# Sheet1.net
KiCad netlist of a schematic drawn in Altium Designer
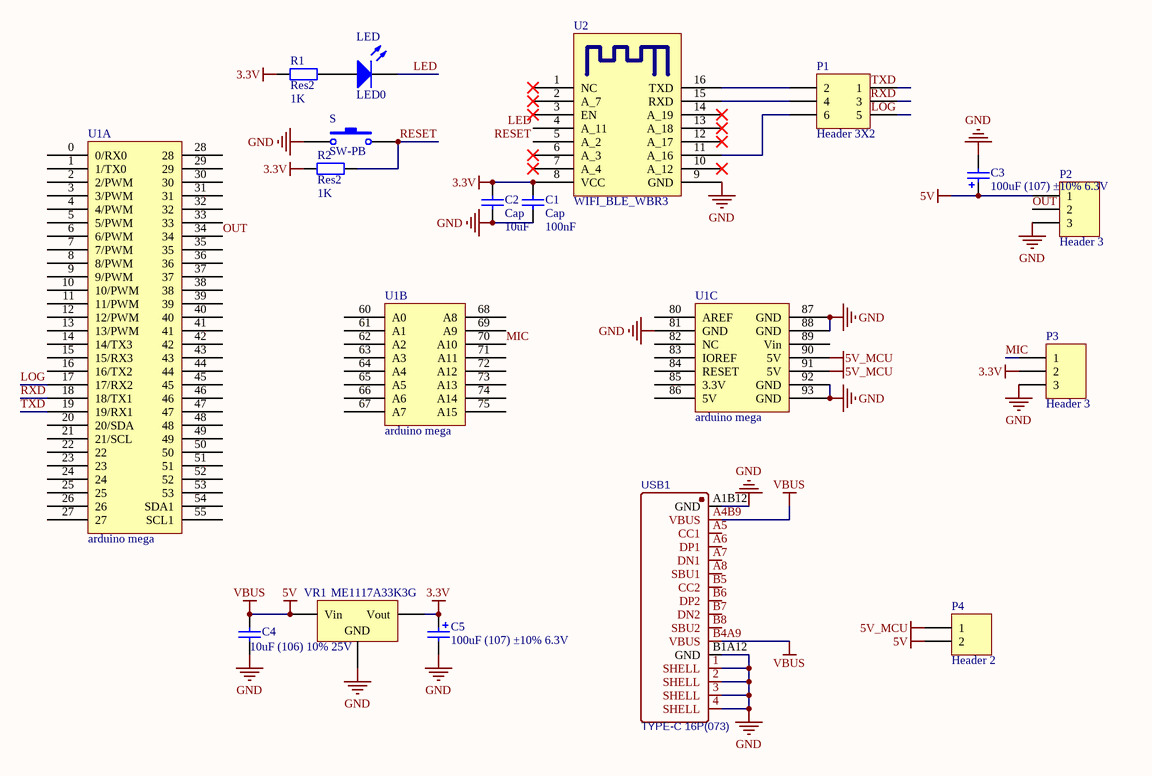
[diagram p0: Sheet1.SchDoc]

(export (version "E")
  (design (tool "Eeschema 10.0.6"))
  (components
    (comp (ref "C1")
      (value "Cap")
      (footprint "C 0603_L")
      (description "Capacitor")
      (fields (field (name "ALTIUM_VALUE") "100nF") (field (name "PUBLISHER") "Altium Limited"))
      (libsource (lib "Miscellaneous Devices") (part "Cap"))
    )
    (comp (ref "C2")
      (value "Cap")
      (footprint "C 0805_L")
      (description "Capacitor")
      (fields (field (name "ALTIUM_VALUE") "10uF") (field (name "PUBLISHER") "Altium Limited"))
      (libsource (lib "Miscellaneous Devices") (part "Cap"))
    )
    (comp (ref "C3")
      (value "100uF (107) ±10% 6.3V")
      (footprint "CASE-B_3528")
      (description "钽电容")
      (libsource (lib "Miscellaneous Devices LC") (part "3528 100uF (107) 10% 6.3V"))
    )
    (comp (ref "C4")
      (value "10uF (106) 10% 25V")
      (footprint "C 0805_L")
      (description "贴片电容")
      (libsource (lib "Miscellaneous Devices LC") (part "0805 10uF (106) 10% 25V"))
    )
    (comp (ref "C5")
      (value "100uF (107) ±10% 6.3V")
      (footprint "CASE-B_3528")
      (description "钽电容")
      (libsource (lib "Miscellaneous Devices LC") (part "3528 100uF (107) 10% 6.3V"))
    )
    (comp (ref "LED")
      (value "LED0")
      (footprint "0603_LED_S1")
      (description "Typical INFRARED GaAs LED")
      (fields (field (name "PUBLISHER") "Altium Limited"))
      (libsource (lib "Miscellaneous Devices") (part "LED0"))
    )
    (comp (ref "P1")
      (value "Header 3X2")
      (footprint "HDR2X3")
      (description "Header, 3-Pin, Dual row")
      (fields (field (name "PUBLISHER") "Altium Limited"))
      (libsource (lib "Miscellaneous Connectors") (part "Header 3X2"))
    )
    (comp (ref "P2")
      (value "Header 3")
      (footprint "HDR1X3")
      (description "Header, 3-Pin")
      (fields (field (name "PUBLISHER") "Altium Limited"))
      (libsource (lib "Miscellaneous Connectors") (part "Header 3"))
    )
    (comp (ref "P3")
      (value "Header 3")
      (footprint "HDR1X3")
      (description "Header, 3-Pin")
      (fields (field (name "PUBLISHER") "Altium Limited"))
      (libsource (lib "Miscellaneous Connectors") (part "Header 3"))
    )
    (comp (ref "P4")
      (value "Header 2")
      (footprint "HDR1X2")
      (description "Header, 2-Pin")
      (fields (field (name "PUBLISHER") "Altium Limited"))
      (libsource (lib "Miscellaneous Connectors") (part "Header 2"))
    )
    (comp (ref "R1")
      (value "Res2")
      (footprint "R 0603_L")
      (description "Resistor")
      (fields (field (name "ALTIUM_VALUE") "1K") (field (name "PUBLISHER") "Altium Limited"))
      (libsource (lib "Miscellaneous Devices") (part "Res2"))
    )
    (comp (ref "R2")
      (value "Res2")
      (footprint "R 0603_L")
      (description "Resistor")
      (fields (field (name "ALTIUM_VALUE") "1K") (field (name "PUBLISHER") "Altium Limited"))
      (libsource (lib "Miscellaneous Devices") (part "Res2"))
    )
    (comp (ref "S")
      (value "SW-PB")
      (footprint "TSW SMD-3*6*2.5")
      (description "Switch")
      (fields (field (name "PUBLISHER") "Altium Limited"))
      (libsource (lib "Miscellaneous Devices") (part "SW-PB"))
    )
    (comp (ref "U1")
      (value "arduino mega")
      (footprint "arduino mega")
      (libsource (lib "Schlib1") (part "arduino mega"))
    )
    (comp (ref "U2")
      (value "WIFI_BLE_WBR3")
      (footprint "WBR3")
      (description "Module")
      (libsource (lib "Schlib1") (part "WBR3"))
    )
    (comp (ref "USB1")
      (value "TYPE-C 16P(073)")
      (footprint "USB-C-SMD_TYPE-C16PIN")
      (fields (field (name "BOM_SUPPLIER PART") "C668624") (field (name "CONTRIBUTOR") "LCSC"))
      (libsource (lib "99999") (part "TYPE-C 16P(073)"))
    )
    (comp (ref "VR1")
      (value "ME1117A33K3G")
      (footprint "TO-252")
      (description "低压差线性稳压(LDO)")
      (libsource (lib "Miscellaneous Devices LC") (part "SOT-223 AMS1117-3.3"))
    )
  )
  (nets
    (net (code "1") (name "/LED") (class "Default")
      (node (ref "LED") (pin "2") (pinfunction "K_2") (pintype "passive"))
      (node (ref "U2") (pin "4") (pinfunction "A_11_4") (pintype "passive"))
    )
    (net (code "2") (name "/LOG") (class "Default")
      (node (ref "P1") (pin "5") (pinfunction "5_5") (pintype "passive"))
      (node (ref "U1") (pin "17") (pinfunction "17/RX2_17") (pintype "passive"))
    )
    (net (code "3") (name "/MIC") (class "Default")
      (node (ref "P3") (pin "1") (pinfunction "1_1") (pintype "passive"))
      (node (ref "U1") (pin "70") (pinfunction "A10_70") (pintype "passive"))
    )
    (net (code "4") (name "/OUT") (class "Default")
      (node (ref "P2") (pin "2") (pinfunction "2_2") (pintype "passive"))
      (node (ref "U1") (pin "34") (pinfunction "34_34") (pintype "passive"))
    )
    (net (code "5") (name "/RESET") (class "Default")
      (node (ref "R2") (pin "2") (pinfunction "2_2") (pintype "passive"))
      (node (ref "S") (pin "2") (pinfunction "2_2") (pintype "passive"))
      (node (ref "U2") (pin "5") (pinfunction "A_2_5") (pintype "passive"))
    )
    (net (code "6") (name "/RXD") (class "Default")
      (node (ref "P1") (pin "3") (pinfunction "3_3") (pintype "passive"))
      (node (ref "U1") (pin "18") (pinfunction "18/TX1_18") (pintype "passive"))
    )
    (net (code "7") (name "/TXD") (class "Default")
      (node (ref "P1") (pin "1") (pinfunction "1_1") (pintype "passive"))
      (node (ref "U1") (pin "19") (pinfunction "19/RX1_19") (pintype "passive"))
    )
    (net (code "8") (name "3.3V") (class "Default")
      (node (ref "C1") (pin "2") (pinfunction "2_2") (pintype "passive"))
      (node (ref "C2") (pin "2") (pinfunction "2_2") (pintype "passive"))
      (node (ref "C5") (pin "1") (pinfunction "1_1") (pintype "passive"))
      (node (ref "P3") (pin "2") (pinfunction "2_2") (pintype "passive"))
      (node (ref "R1") (pin "1") (pinfunction "1_1") (pintype "passive"))
      (node (ref "R2") (pin "1") (pinfunction "1_1") (pintype "passive"))
      (node (ref "U2") (pin "8") (pinfunction "VCC_8") (pintype "passive"))
      (node (ref "VR1") (pin "2") (pinfunction "Vout_2") (pintype "passive"))
    )
    (net (code "9") (name "5V") (class "Default")
      (node (ref "C3") (pin "1") (pinfunction "1_1") (pintype "passive"))
      (node (ref "C4") (pin "2") (pinfunction "2_2") (pintype "passive"))
      (node (ref "P2") (pin "1") (pinfunction "1_1") (pintype "passive"))
      (node (ref "P4") (pin "2") (pinfunction "2_2") (pintype "passive"))
      (node (ref "USB1") (pin "A4B9") (pinfunction "VBUS_A4B9") (pintype "passive"))
      (node (ref "USB1") (pin "B4A9") (pinfunction "VBUS_B4A9") (pintype "passive"))
      (node (ref "VR1") (pin "3") (pinfunction "Vin_3") (pintype "passive"))
    )
    (net (code "10") (name "5V_MCU") (class "Default")
      (node (ref "P4") (pin "1") (pinfunction "1_1") (pintype "passive"))
      (node (ref "U1") (pin "90") (pinfunction "5V_90") (pintype "passive"))
      (node (ref "U1") (pin "91") (pinfunction "5V_91") (pintype "passive"))
    )
    (net (code "11") (name "GND") (class "Default")
      (node (ref "C1") (pin "1") (pinfunction "1_1") (pintype "passive"))
      (node (ref "C2") (pin "1") (pinfunction "1_1") (pintype "passive"))
      (node (ref "C3") (pin "2") (pinfunction "2_2") (pintype "passive"))
      (node (ref "C4") (pin "1") (pinfunction "1_1") (pintype "passive"))
      (node (ref "C5") (pin "2") (pinfunction "2_2") (pintype "passive"))
      (node (ref "P2") (pin "3") (pinfunction "3_3") (pintype "passive"))
      (node (ref "P3") (pin "3") (pinfunction "3_3") (pintype "passive"))
      (node (ref "S") (pin "1") (pinfunction "1_1") (pintype "passive"))
      (node (ref "U1") (pin "81") (pinfunction "GND_81") (pintype "passive"))
      (node (ref "U1") (pin "87") (pinfunction "GND_87") (pintype "passive"))
      (node (ref "U1") (pin "88") (pinfunction "GND_88") (pintype "passive"))
      (node (ref "U1") (pin "92") (pinfunction "GND_92") (pintype "passive"))
      (node (ref "U1") (pin "93") (pinfunction "GND_93") (pintype "passive"))
      (node (ref "U2") (pin "9") (pinfunction "GND_9") (pintype "passive"))
      (node (ref "USB1") (pin "1") (pinfunction "SHELL_1") (pintype "passive"))
      (node (ref "USB1") (pin "2") (pinfunction "SHELL_2") (pintype "passive"))
      (node (ref "USB1") (pin "3") (pinfunction "SHELL_3") (pintype "passive"))
      (node (ref "USB1") (pin "4") (pinfunction "SHELL_4") (pintype "passive"))
      (node (ref "USB1") (pin "A1B12") (pinfunction "GND_A1B12") (pintype "passive"))
      (node (ref "USB1") (pin "B1A12") (pinfunction "GND_B1A12") (pintype "passive"))
      (node (ref "VR1") (pin "1") (pinfunction "GND_1") (pintype "passive"))
    )
    (net (code "12") (name "Net-(LED-A)") (class "Default")
      (node (ref "LED") (pin "1") (pinfunction "A_1") (pintype "passive"))
      (node (ref "R1") (pin "2") (pinfunction "2_2") (pintype "passive"))
    )
    (net (code "13") (name "Net-(U2-A_16)") (class "Default")
      (node (ref "P1") (pin "6") (pinfunction "6_6") (pintype "passive"))
      (node (ref "U2") (pin "11") (pinfunction "A_16_11") (pintype "passive"))
    )
    (net (code "14") (name "Net-(U2-RXD)") (class "Default")
      (node (ref "P1") (pin "4") (pinfunction "4_4") (pintype "passive"))
      (node (ref "U2") (pin "15") (pinfunction "RXD_15") (pintype "passive"))
    )
    (net (code "15") (name "Net-(U2-TXD)") (class "Default")
      (node (ref "P1") (pin "2") (pinfunction "2_2") (pintype "passive"))
      (node (ref "U2") (pin "16") (pinfunction "TXD_16") (pintype "passive"))
    )
    (net (code "16") (name "unconnected-(U1-Pad22)") (class "Default")
      (node (ref "U1") (pin "22") (pinfunction "22_22") (pintype "passive"))
    )
    (net (code "17") (name "unconnected-(U1-Pad23)") (class "Default")
      (node (ref "U1") (pin "23") (pinfunction "23_23") (pintype "passive"))
    )
    (net (code "18") (name "unconnected-(U1-Pad24)") (class "Default")
      (node (ref "U1") (pin "24") (pinfunction "24_24") (pintype "passive"))
    )
    (net (code "19") (name "unconnected-(U1-Pad25)") (class "Default")
      (node (ref "U1") (pin "25") (pinfunction "25_25") (pintype "passive"))
    )
    (net (code "20") (name "unconnected-(U1-Pad26)") (class "Default")
      (node (ref "U1") (pin "26") (pinfunction "26_26") (pintype "passive"))
    )
    (net (code "21") (name "unconnected-(U1-Pad27)") (class "Default")
      (node (ref "U1") (pin "27") (pinfunction "27_27") (pintype "passive"))
    )
    (net (code "22") (name "unconnected-(U1-Pad28)") (class "Default")
      (node (ref "U1") (pin "28") (pinfunction "28_28") (pintype "passive"))
    )
    (net (code "23") (name "unconnected-(U1-Pad29)") (class "Default")
      (node (ref "U1") (pin "29") (pinfunction "29_29") (pintype "passive"))
    )
    (net (code "24") (name "unconnected-(U1-Pad30)") (class "Default")
      (node (ref "U1") (pin "30") (pinfunction "30_30") (pintype "passive"))
    )
    (net (code "25") (name "unconnected-(U1-Pad31)") (class "Default")
      (node (ref "U1") (pin "31") (pinfunction "31_31") (pintype "passive"))
    )
    (net (code "26") (name "unconnected-(U1-Pad32)") (class "Default")
      (node (ref "U1") (pin "32") (pinfunction "32_32") (pintype "passive"))
    )
    (net (code "27") (name "unconnected-(U1-Pad33)") (class "Default")
      (node (ref "U1") (pin "33") (pinfunction "33_33") (pintype "passive"))
    )
    (net (code "28") (name "unconnected-(U1-Pad35)") (class "Default")
      (node (ref "U1") (pin "35") (pinfunction "35_35") (pintype "passive"))
    )
    (net (code "29") (name "unconnected-(U1-Pad36)") (class "Default")
      (node (ref "U1") (pin "36") (pinfunction "36_36") (pintype "passive"))
    )
    (net (code "30") (name "unconnected-(U1-Pad37)") (class "Default")
      (node (ref "U1") (pin "37") (pinfunction "37_37") (pintype "passive"))
    )
    (net (code "31") (name "unconnected-(U1-Pad38)") (class "Default")
      (node (ref "U1") (pin "38") (pinfunction "38_38") (pintype "passive"))
    )
    (net (code "32") (name "unconnected-(U1-Pad39)") (class "Default")
      (node (ref "U1") (pin "39") (pinfunction "39_39") (pintype "passive"))
    )
    (net (code "33") (name "unconnected-(U1-Pad40)") (class "Default")
      (node (ref "U1") (pin "40") (pinfunction "40_40") (pintype "passive"))
    )
    (net (code "34") (name "unconnected-(U1-Pad41)") (class "Default")
      (node (ref "U1") (pin "41") (pinfunction "41_41") (pintype "passive"))
    )
    (net (code "35") (name "unconnected-(U1-Pad42)") (class "Default")
      (node (ref "U1") (pin "42") (pinfunction "42_42") (pintype "passive"))
    )
    (net (code "36") (name "unconnected-(U1-Pad43)") (class "Default")
      (node (ref "U1") (pin "43") (pinfunction "43_43") (pintype "passive"))
    )
    (net (code "37") (name "unconnected-(U1-Pad44)") (class "Default")
      (node (ref "U1") (pin "44") (pinfunction "44_44") (pintype "passive"))
    )
    (net (code "38") (name "unconnected-(U1-Pad45)") (class "Default")
      (node (ref "U1") (pin "45") (pinfunction "45_45") (pintype "passive"))
    )
    (net (code "39") (name "unconnected-(U1-Pad46)") (class "Default")
      (node (ref "U1") (pin "46") (pinfunction "46_46") (pintype "passive"))
    )
    (net (code "40") (name "unconnected-(U1-Pad47)") (class "Default")
      (node (ref "U1") (pin "47") (pinfunction "47_47") (pintype "passive"))
    )
    (net (code "41") (name "unconnected-(U1-Pad48)") (class "Default")
      (node (ref "U1") (pin "48") (pinfunction "48_48") (pintype "passive"))
    )
    (net (code "42") (name "unconnected-(U1-Pad49)") (class "Default")
      (node (ref "U1") (pin "49") (pinfunction "49_49") (pintype "passive"))
    )
    (net (code "43") (name "unconnected-(U1-Pad50)") (class "Default")
      (node (ref "U1") (pin "50") (pinfunction "50_50") (pintype "passive"))
    )
    (net (code "44") (name "unconnected-(U1-Pad51)") (class "Default")
      (node (ref "U1") (pin "51") (pinfunction "51_51") (pintype "passive"))
    )
    (net (code "45") (name "unconnected-(U1-Pad52)") (class "Default")
      (node (ref "U1") (pin "52") (pinfunction "52_52") (pintype "passive"))
    )
    (net (code "46") (name "unconnected-(U1-Pad53)") (class "Default")
      (node (ref "U1") (pin "53") (pinfunction "53_53") (pintype "passive"))
    )
    (net (code "47") (name "unconnected-(U1A-0{slash}RX0-Pad0)") (class "Default")
      (node (ref "U1") (pin "0") (pinfunction "0/RX0_0") (pintype "passive"))
    )
    (net (code "48") (name "unconnected-(U1A-1{slash}TX0-Pad1)") (class "Default")
      (node (ref "U1") (pin "1") (pinfunction "1/TX0_1") (pintype "passive"))
    )
    (net (code "49") (name "unconnected-(U1A-2{slash}PWM-Pad2)") (class "Default")
      (node (ref "U1") (pin "2") (pinfunction "2/PWM_2") (pintype "passive"))
    )
    (net (code "50") (name "unconnected-(U1A-3{slash}PWM-Pad3)") (class "Default")
      (node (ref "U1") (pin "3") (pinfunction "3/PWM_3") (pintype "passive"))
    )
    (net (code "51") (name "unconnected-(U1A-4{slash}PWM-Pad4)") (class "Default")
      (node (ref "U1") (pin "4") (pinfunction "4/PWM_4") (pintype "passive"))
    )
    (net (code "52") (name "unconnected-(U1A-5{slash}PWM-Pad5)") (class "Default")
      (node (ref "U1") (pin "5") (pinfunction "5/PWM_5") (pintype "passive"))
    )
    (net (code "53") (name "unconnected-(U1A-6{slash}PWM-Pad6)") (class "Default")
      (node (ref "U1") (pin "6") (pinfunction "6/PWM_6") (pintype "passive"))
    )
    (net (code "54") (name "unconnected-(U1A-7{slash}PWM-Pad7)") (class "Default")
      (node (ref "U1") (pin "7") (pinfunction "7/PWM_7") (pintype "passive"))
    )
    (net (code "55") (name "unconnected-(U1A-8{slash}PWM-Pad8)") (class "Default")
      (node (ref "U1") (pin "8") (pinfunction "8/PWM_8") (pintype "passive"))
    )
    (net (code "56") (name "unconnected-(U1A-9{slash}PWM-Pad9)") (class "Default")
      (node (ref "U1") (pin "9") (pinfunction "9/PWM_9") (pintype "passive"))
    )
    (net (code "57") (name "unconnected-(U1A-10{slash}PWM-Pad10)") (class "Default")
      (node (ref "U1") (pin "10") (pinfunction "10/PWM_10") (pintype "passive"))
    )
    (net (code "58") (name "unconnected-(U1A-11{slash}PWM-Pad11)") (class "Default")
      (node (ref "U1") (pin "11") (pinfunction "11/PWM_11") (pintype "passive"))
    )
    (net (code "59") (name "unconnected-(U1A-12{slash}PWM-Pad12)") (class "Default")
      (node (ref "U1") (pin "12") (pinfunction "12/PWM_12") (pintype "passive"))
    )
    (net (code "60") (name "unconnected-(U1A-13{slash}PWM-Pad13)") (class "Default")
      (node (ref "U1") (pin "13") (pinfunction "13/PWM_13") (pintype "passive"))
    )
    (net (code "61") (name "unconnected-(U1A-14{slash}TX3-Pad14)") (class "Default")
      (node (ref "U1") (pin "14") (pinfunction "14/TX3_14") (pintype "passive"))
    )
    (net (code "62") (name "unconnected-(U1A-15{slash}RX3-Pad15)") (class "Default")
      (node (ref "U1") (pin "15") (pinfunction "15/RX3_15") (pintype "passive"))
    )
    (net (code "63") (name "unconnected-(U1A-16{slash}TX2-Pad16)") (class "Default")
      (node (ref "U1") (pin "16") (pinfunction "16/TX2_16") (pintype "passive"))
    )
    (net (code "64") (name "unconnected-(U1A-20{slash}SDA-Pad20)") (class "Default")
      (node (ref "U1") (pin "20") (pinfunction "20/SDA_20") (pintype "passive"))
    )
    (net (code "65") (name "unconnected-(U1A-21{slash}SCL-Pad21)") (class "Default")
      (node (ref "U1") (pin "21") (pinfunction "21/SCL_21") (pintype "passive"))
    )
    (net (code "66") (name "unconnected-(U1A-SCL1-Pad55)") (class "Default")
      (node (ref "U1") (pin "55") (pinfunction "SCL1_55") (pintype "passive"))
    )
    (net (code "67") (name "unconnected-(U1A-SDA1-Pad54)") (class "Default")
      (node (ref "U1") (pin "54") (pinfunction "SDA1_54") (pintype "passive"))
    )
    (net (code "68") (name "unconnected-(U1B-A0-Pad60)") (class "Default")
      (node (ref "U1") (pin "60") (pinfunction "A0_60") (pintype "passive"))
    )
    (net (code "69") (name "unconnected-(U1B-A1-Pad61)") (class "Default")
      (node (ref "U1") (pin "61") (pinfunction "A1_61") (pintype "passive"))
    )
    (net (code "70") (name "unconnected-(U1B-A2-Pad62)") (class "Default")
      (node (ref "U1") (pin "62") (pinfunction "A2_62") (pintype "passive"))
    )
    (net (code "71") (name "unconnected-(U1B-A3-Pad63)") (class "Default")
      (node (ref "U1") (pin "63") (pinfunction "A3_63") (pintype "passive"))
    )
    (net (code "72") (name "unconnected-(U1B-A4-Pad64)") (class "Default")
      (node (ref "U1") (pin "64") (pinfunction "A4_64") (pintype "passive"))
    )
    (net (code "73") (name "unconnected-(U1B-A5-Pad65)") (class "Default")
      (node (ref "U1") (pin "65") (pinfunction "A5_65") (pintype "passive"))
    )
    (net (code "74") (name "unconnected-(U1B-A6-Pad66)") (class "Default")
      (node (ref "U1") (pin "66") (pinfunction "A6_66") (pintype "passive"))
    )
    (net (code "75") (name "unconnected-(U1B-A7-Pad67)") (class "Default")
      (node (ref "U1") (pin "67") (pinfunction "A7_67") (pintype "passive"))
    )
    (net (code "76") (name "unconnected-(U1B-A8-Pad68)") (class "Default")
      (node (ref "U1") (pin "68") (pinfunction "A8_68") (pintype "passive"))
    )
    (net (code "77") (name "unconnected-(U1B-A9-Pad69)") (class "Default")
      (node (ref "U1") (pin "69") (pinfunction "A9_69") (pintype "passive"))
    )
    (net (code "78") (name "unconnected-(U1B-A11-Pad71)") (class "Default")
      (node (ref "U1") (pin "71") (pinfunction "A11_71") (pintype "passive"))
    )
    (net (code "79") (name "unconnected-(U1B-A12-Pad72)") (class "Default")
      (node (ref "U1") (pin "72") (pinfunction "A12_72") (pintype "passive"))
    )
    (net (code "80") (name "unconnected-(U1B-A13-Pad73)") (class "Default")
      (node (ref "U1") (pin "73") (pinfunction "A13_73") (pintype "passive"))
    )
    (net (code "81") (name "unconnected-(U1B-A14-Pad74)") (class "Default")
      (node (ref "U1") (pin "74") (pinfunction "A14_74") (pintype "passive"))
    )
    (net (code "82") (name "unconnected-(U1B-A15-Pad75)") (class "Default")
      (node (ref "U1") (pin "75") (pinfunction "A15_75") (pintype "passive"))
    )
    (net (code "83") (name "unconnected-(U1C-3.3V-Pad85)") (class "Default")
      (node (ref "U1") (pin "85") (pinfunction "3.3V_85") (pintype "passive"))
    )
    (net (code "84") (name "unconnected-(U1C-5V-Pad86)") (class "Default")
      (node (ref "U1") (pin "86") (pinfunction "5V_86") (pintype "passive"))
    )
    (net (code "85") (name "unconnected-(U1C-AREF-Pad80)") (class "Default")
      (node (ref "U1") (pin "80") (pinfunction "AREF_80") (pintype "passive"))
    )
    (net (code "86") (name "unconnected-(U1C-IOREF-Pad83)") (class "Default")
      (node (ref "U1") (pin "83") (pinfunction "IOREF_83") (pintype "passive"))
    )
    (net (code "87") (name "unconnected-(U1C-NC-Pad82)") (class "Default")
      (node (ref "U1") (pin "82") (pinfunction "NC_82") (pintype "passive"))
    )
    (net (code "88") (name "unconnected-(U1C-RESET-Pad84)") (class "Default")
      (node (ref "U1") (pin "84") (pinfunction "RESET_84") (pintype "passive"))
    )
    (net (code "89") (name "unconnected-(U1C-Vin-Pad89)") (class "Default")
      (node (ref "U1") (pin "89") (pinfunction "Vin_89") (pintype "passive"))
    )
    (net (code "90") (name "unconnected-(U2-A_3-Pad6)") (class "Default")
      (node (ref "U2") (pin "6") (pinfunction "A_3_6") (pintype "passive+no_connect"))
    )
    (net (code "91") (name "unconnected-(U2-A_4-Pad7)") (class "Default")
      (node (ref "U2") (pin "7") (pinfunction "A_4_7") (pintype "passive+no_connect"))
    )
    (net (code "92") (name "unconnected-(U2-A_7-Pad2)") (class "Default")
      (node (ref "U2") (pin "2") (pinfunction "A_7_2") (pintype "passive+no_connect"))
    )
    (net (code "93") (name "unconnected-(U2-A_12-Pad10)") (class "Default")
      (node (ref "U2") (pin "10") (pinfunction "A_12_10") (pintype "passive+no_connect"))
    )
    (net (code "94") (name "unconnected-(U2-A_17-Pad12)") (class "Default")
      (node (ref "U2") (pin "12") (pinfunction "A_17_12") (pintype "passive+no_connect"))
    )
    (net (code "95") (name "unconnected-(U2-A_18-Pad13)") (class "Default")
      (node (ref "U2") (pin "13") (pinfunction "A_18_13") (pintype "passive+no_connect"))
    )
    (net (code "96") (name "unconnected-(U2-A_19-Pad14)") (class "Default")
      (node (ref "U2") (pin "14") (pinfunction "A_19_14") (pintype "passive+no_connect"))
    )
    (net (code "97") (name "unconnected-(U2-EN-Pad3)") (class "Default")
      (node (ref "U2") (pin "3") (pinfunction "EN_3") (pintype "passive+no_connect"))
    )
    (net (code "98") (name "unconnected-(U2-NC-Pad1)") (class "Default")
      (node (ref "U2") (pin "1") (pinfunction "NC_1") (pintype "passive+no_connect"))
    )
    (net (code "99") (name "unconnected-(USB1-CC1-PadA5)") (class "Default")
      (node (ref "USB1") (pin "A5") (pinfunction "CC1_A5") (pintype "passive"))
    )
    (net (code "100") (name "unconnected-(USB1-CC2-PadB5)") (class "Default")
      (node (ref "USB1") (pin "B5") (pinfunction "CC2_B5") (pintype "passive"))
    )
    (net (code "101") (name "unconnected-(USB1-DN1-PadA7)") (class "Default")
      (node (ref "USB1") (pin "A7") (pinfunction "DN1_A7") (pintype "passive"))
    )
    (net (code "102") (name "unconnected-(USB1-DN2-PadB7)") (class "Default")
      (node (ref "USB1") (pin "B7") (pinfunction "DN2_B7") (pintype "passive"))
    )
    (net (code "103") (name "unconnected-(USB1-DP1-PadA6)") (class "Default")
      (node (ref "USB1") (pin "A6") (pinfunction "DP1_A6") (pintype "passive"))
    )
    (net (code "104") (name "unconnected-(USB1-DP2-PadB6)") (class "Default")
      (node (ref "USB1") (pin "B6") (pinfunction "DP2_B6") (pintype "passive"))
    )
    (net (code "105") (name "unconnected-(USB1-SBU1-PadA8)") (class "Default")
      (node (ref "USB1") (pin "A8") (pinfunction "SBU1_A8") (pintype "passive"))
    )
    (net (code "106") (name "unconnected-(USB1-SBU2-PadB8)") (class "Default")
      (node (ref "USB1") (pin "B8") (pinfunction "SBU2_B8") (pintype "passive"))
    )
  )
)
